# brd.net
KiCad netlist of a schematic drawn in EAGLE
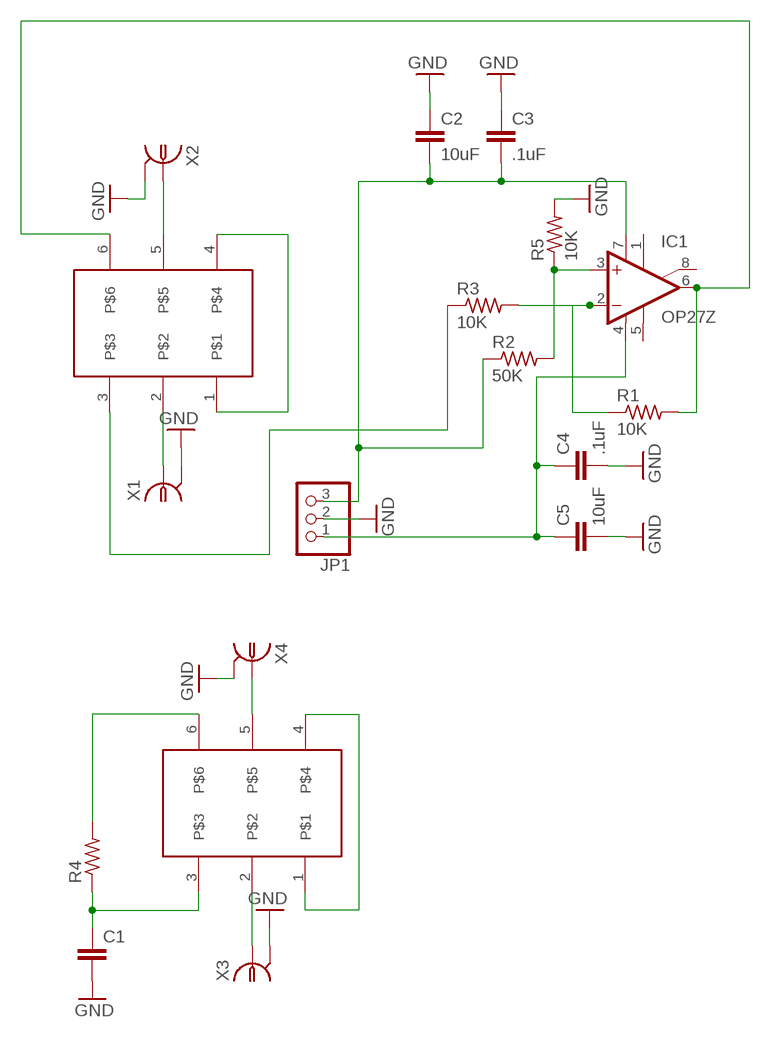
[diagram p0: schematic, sheet 1]

(export (version "E")
  (design (tool "Eeschema 10.0.6"))
  (components
    (comp (ref "C1")
      (value "C-EU025-024X044")
      (footprint "eagle-import:C025-024X044")
      (libsource (lib "eagle-import") (part "C-EU025-024X044"))
    )
    (comp (ref "C2")
      (value "10uF")
      (footprint "eagle-import:C025-024X044")
      (libsource (lib "eagle-import") (part "C-EU025-024X044"))
    )
    (comp (ref "C3")
      (value ".1uF")
      (footprint "eagle-import:C025-024X044")
      (libsource (lib "eagle-import") (part "C-EU025-024X044"))
    )
    (comp (ref "C4")
      (value ".1uF")
      (footprint "eagle-import:C025-024X044")
      (libsource (lib "eagle-import") (part "C-EU025-024X044"))
    )
    (comp (ref "C5")
      (value "10uF")
      (footprint "eagle-import:C025-024X044")
      (libsource (lib "eagle-import") (part "C-EU025-024X044"))
    )
    (comp (ref "IC1")
      (value "OP27Z")
      (footprint "eagle-import:DIL08")
      (libsource (lib "eagle-import") (part "OP27Z"))
    )
    (comp (ref "JP1")
      (value "PINHD-1X3")
      (footprint "eagle-import:1X03")
      (libsource (lib "eagle-import") (part "PINHD-1X3"))
    )
    (comp (ref "R1")
      (value "10K")
      (footprint "eagle-import:0204V")
      (libsource (lib "eagle-import") (part "R-US_0204/2V"))
    )
    (comp (ref "R2")
      (value "50K")
      (footprint "eagle-import:0204V")
      (libsource (lib "eagle-import") (part "R-US_0204/2V"))
    )
    (comp (ref "R3")
      (value "10K")
      (footprint "eagle-import:0204V")
      (libsource (lib "eagle-import") (part "R-US_0204/2V"))
    )
    (comp (ref "R4")
      (value "R-US_0204/2V")
      (footprint "eagle-import:0204V")
      (libsource (lib "eagle-import") (part "R-US_0204/2V"))
    )
    (comp (ref "R5")
      (value "10K")
      (footprint "eagle-import:0204V")
      (libsource (lib "eagle-import") (part "R-US_0204/2V"))
    )
    (comp (ref "U$1")
      (value "DP3T-TOGGLE")
      (footprint "eagle-import:7201MD9AV2BE")
      (libsource (lib "eagle-import") (part "DP3T-TOGGLE"))
    )
    (comp (ref "U$2")
      (value "DP3T-TOGGLE")
      (footprint "eagle-import:7201MD9AV2BE")
      (libsource (lib "eagle-import") (part "DP3T-TOGGLE"))
    )
    (comp (ref "X1")
      (value "BNC-H")
      (footprint "eagle-import:BNC90")
      (libsource (lib "eagle-import") (part "BNC-H"))
    )
    (comp (ref "X2")
      (value "BNC-H")
      (footprint "eagle-import:BNC90")
      (libsource (lib "eagle-import") (part "BNC-H"))
    )
    (comp (ref "X3")
      (value "BNC-H")
      (footprint "eagle-import:BNC90")
      (libsource (lib "eagle-import") (part "BNC-H"))
    )
    (comp (ref "X4")
      (value "BNC-H")
      (footprint "eagle-import:BNC90")
      (libsource (lib "eagle-import") (part "BNC-H"))
    )
  )
  (nets
    (net (code "1") (name "GND") (class "Default")
      (node (ref "C1") (pin "2") (pinfunction "2_2") (pintype "passive"))
      (node (ref "C2") (pin "1") (pinfunction "1_1") (pintype "passive"))
      (node (ref "C3") (pin "1") (pinfunction "1_1") (pintype "passive"))
      (node (ref "C4") (pin "2") (pinfunction "2_2") (pintype "passive"))
      (node (ref "C5") (pin "2") (pinfunction "2_2") (pintype "passive"))
      (node (ref "JP1") (pin "2") (pinfunction "2_2") (pintype "passive"))
      (node (ref "R5") (pin "2") (pinfunction "2_2") (pintype "passive"))
      (node (ref "X1") (pin "2") (pinfunction "2_2") (pintype "passive"))
      (node (ref "X2") (pin "2") (pinfunction "2_2") (pintype "passive"))
      (node (ref "X3") (pin "2") (pinfunction "2_2") (pintype "passive"))
      (node (ref "X4") (pin "2") (pinfunction "2_2") (pintype "passive"))
    )
    (net (code "2") (name "Net-(IC1-+IN)") (class "Default")
      (node (ref "IC1") (pin "3") (pinfunction "+IN_3") (pintype "input"))
      (node (ref "R2") (pin "2") (pinfunction "2_2") (pintype "passive"))
      (node (ref "R5") (pin "1") (pinfunction "1_1") (pintype "passive"))
    )
    (net (code "3") (name "Net-(IC1--IN)") (class "Default")
      (node (ref "IC1") (pin "2") (pinfunction "-IN_2") (pintype "input"))
      (node (ref "R1") (pin "1") (pinfunction "1_1") (pintype "passive"))
      (node (ref "R3") (pin "2") (pinfunction "2_2") (pintype "passive"))
    )
    (net (code "4") (name "Net-(IC1-OUT)") (class "Default")
      (node (ref "IC1") (pin "6") (pinfunction "OUT_6") (pintype "output"))
      (node (ref "R1") (pin "2") (pinfunction "2_2") (pintype "passive"))
      (node (ref "U$1") (pin "6") (pinfunction "P$6_6") (pintype "bidirectional"))
    )
    (net (code "5") (name "Net-(IC1-V+)") (class "Default")
      (node (ref "C2") (pin "2") (pinfunction "2_2") (pintype "passive"))
      (node (ref "C3") (pin "2") (pinfunction "2_2") (pintype "passive"))
      (node (ref "IC1") (pin "7") (pinfunction "V+_7") (pintype "power_in"))
      (node (ref "JP1") (pin "3") (pinfunction "3_3") (pintype "passive"))
      (node (ref "R2") (pin "1") (pinfunction "1_1") (pintype "passive"))
    )
    (net (code "6") (name "Net-(IC1-V-)") (class "Default")
      (node (ref "C4") (pin "1") (pinfunction "1_1") (pintype "passive"))
      (node (ref "C5") (pin "1") (pinfunction "1_1") (pintype "passive"))
      (node (ref "IC1") (pin "4") (pinfunction "V-_4") (pintype "power_in"))
      (node (ref "JP1") (pin "1") (pinfunction "1_1") (pintype "passive"))
    )
    (net (code "7") (name "Net-(U$1-P$1)") (class "Default")
      (node (ref "U$1") (pin "1") (pinfunction "P$1_1") (pintype "bidirectional"))
      (node (ref "U$1") (pin "4") (pinfunction "P$4_4") (pintype "bidirectional"))
    )
    (net (code "8") (name "Net-(U$1-P$2)") (class "Default")
      (node (ref "U$1") (pin "2") (pinfunction "P$2_2") (pintype "bidirectional"))
      (node (ref "X1") (pin "1") (pinfunction "1_1") (pintype "passive"))
    )
    (net (code "9") (name "Net-(U$1-P$3)") (class "Default")
      (node (ref "R3") (pin "1") (pinfunction "1_1") (pintype "passive"))
      (node (ref "U$1") (pin "3") (pinfunction "P$3_3") (pintype "bidirectional"))
    )
    (net (code "10") (name "Net-(U$1-P$5)") (class "Default")
      (node (ref "U$1") (pin "5") (pinfunction "P$5_5") (pintype "bidirectional"))
      (node (ref "X2") (pin "1") (pinfunction "1_1") (pintype "passive"))
    )
    (net (code "11") (name "Net-(U$2-P$1)") (class "Default")
      (node (ref "U$2") (pin "1") (pinfunction "P$1_1") (pintype "bidirectional"))
      (node (ref "U$2") (pin "4") (pinfunction "P$4_4") (pintype "bidirectional"))
    )
    (net (code "12") (name "Net-(U$2-P$2)") (class "Default")
      (node (ref "U$2") (pin "2") (pinfunction "P$2_2") (pintype "bidirectional"))
      (node (ref "X3") (pin "1") (pinfunction "1_1") (pintype "passive"))
    )
    (net (code "13") (name "Net-(U$2-P$3)") (class "Default")
      (node (ref "C1") (pin "1") (pinfunction "1_1") (pintype "passive"))
      (node (ref "R4") (pin "1") (pinfunction "1_1") (pintype "passive"))
      (node (ref "U$2") (pin "3") (pinfunction "P$3_3") (pintype "bidirectional"))
    )
    (net (code "14") (name "Net-(U$2-P$5)") (class "Default")
      (node (ref "U$2") (pin "5") (pinfunction "P$5_5") (pintype "bidirectional"))
      (node (ref "X4") (pin "1") (pinfunction "1_1") (pintype "passive"))
    )
    (net (code "15") (name "Net-(U$2-P$6)") (class "Default")
      (node (ref "R4") (pin "2") (pinfunction "2_2") (pintype "passive"))
      (node (ref "U$2") (pin "6") (pinfunction "P$6_6") (pintype "bidirectional"))
    )
    (net (code "16") (name "unconnected-(IC1-ON1-Pad1)") (class "Default")
      (node (ref "IC1") (pin "1") (pinfunction "ON1_1") (pintype "passive"))
    )
    (net (code "17") (name "unconnected-(IC1-ON2-Pad8)") (class "Default")
      (node (ref "IC1") (pin "8") (pinfunction "ON2_8") (pintype "passive"))
    )
    (net (code "18") (name "unconnected-(IC1-OPT-Pad5)") (class "Default")
      (node (ref "IC1") (pin "5") (pinfunction "OPT_5") (pintype "passive"))
    )
  )
)
